# ESP32dj.net
KiCad netlist of a schematic drawn in EasyEDA Pro
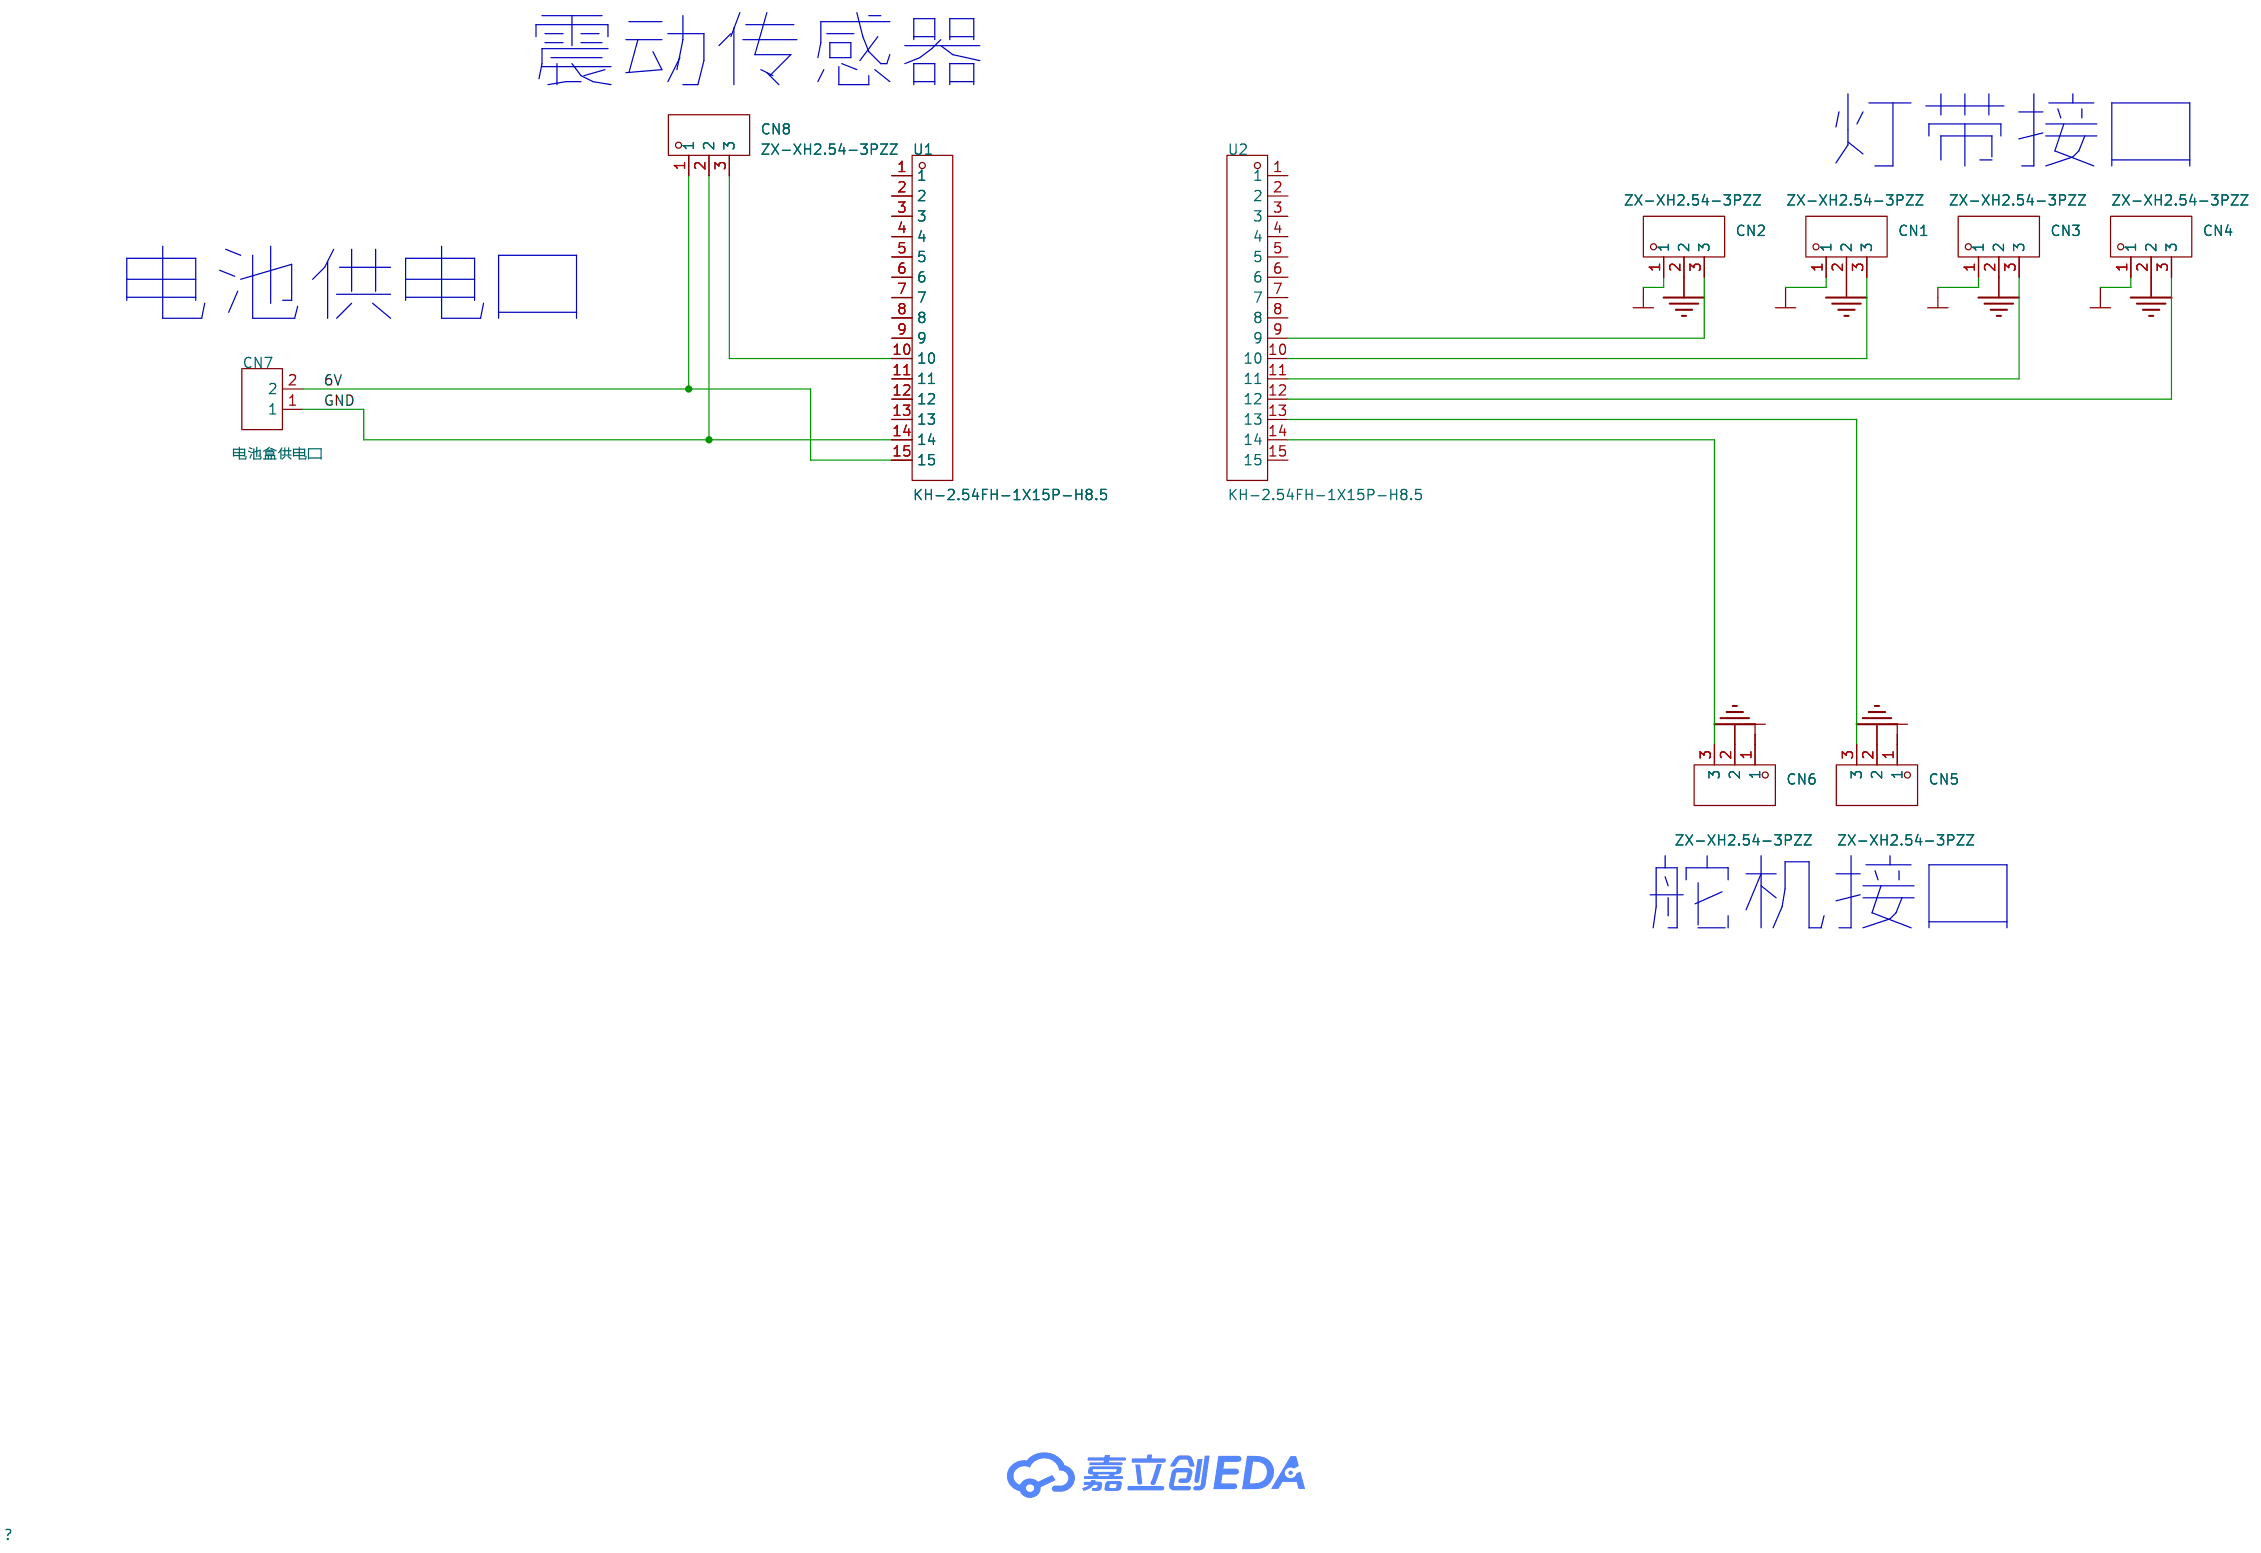
[diagram p0: schematic sheet]

(export (version "E")
  (design (tool "Eeschema 10.0.6"))
  (components
    (comp (ref "CN1")
      (value "ZX-XH2.54-3PZZ")
      (footprint "easyedapro:CONN-TH_3P-P2.54_2501S-3P")
      (fields (field (name "Manufacturer") "Megastar(兆星)"))
      (libsource (lib "easyedapro") (part "ZX-XH2.54-3PZZ"))
    )
    (comp (ref "CN2")
      (value "ZX-XH2.54-3PZZ")
      (footprint "easyedapro:CONN-TH_3P-P2.54_2501S-3P")
      (fields (field (name "Manufacturer") "Megastar(兆星)"))
      (libsource (lib "easyedapro") (part "ZX-XH2.54-3PZZ"))
    )
    (comp (ref "CN3")
      (value "ZX-XH2.54-3PZZ")
      (footprint "easyedapro:CONN-TH_3P-P2.54_2501S-3P")
      (fields (field (name "Manufacturer") "Megastar(兆星)"))
      (libsource (lib "easyedapro") (part "ZX-XH2.54-3PZZ"))
    )
    (comp (ref "CN4")
      (value "ZX-XH2.54-3PZZ")
      (footprint "easyedapro:CONN-TH_3P-P2.54_2501S-3P")
      (fields (field (name "Manufacturer") "Megastar(兆星)"))
      (libsource (lib "easyedapro") (part "ZX-XH2.54-3PZZ"))
    )
    (comp (ref "CN5")
      (value "ZX-XH2.54-3PZZ")
      (footprint "easyedapro:CONN-TH_3P-P2.54_2501S-3P")
      (fields (field (name "Manufacturer") "Megastar(兆星)"))
      (libsource (lib "easyedapro") (part "ZX-XH2.54-3PZZ"))
    )
    (comp (ref "CN6")
      (value "ZX-XH2.54-3PZZ")
      (footprint "easyedapro:CONN-TH_3P-P2.54_2501S-3P")
      (fields (field (name "Manufacturer") "Megastar(兆星)"))
      (libsource (lib "easyedapro") (part "ZX-XH2.54-3PZZ"))
    )
    (comp (ref "CN7")
      (value "电池盒供电口")
      (footprint "easyedapro:CONN-TH_2P-P2.50_BX-XH2.54-2PZZ")
      (fields (field (name "Manufacturer") "Bossie(博锡)"))
      (libsource (lib "easyedapro") (part "BX-XH2.54-2PZZ"))
    )
    (comp (ref "CN8")
      (value "ZX-XH2.54-3PZZ")
      (footprint "easyedapro:CONN-TH_3P-P2.54_2501S-3P")
      (fields (field (name "Manufacturer") "Megastar(兆星)"))
      (libsource (lib "easyedapro") (part "ZX-XH2.54-3PZZ"))
    )
    (comp (ref "U1")
      (value "KH-2.54FH-1X15P-H8.5")
      (footprint "easyedapro:HDR-TH_15P-P2.54-V-F")
      (fields (field (name "Manufacturer") "kinghelm(金航标)"))
      (libsource (lib "easyedapro") (part "KH-2.54FH-1X15P-H8.5"))
    )
    (comp (ref "U2")
      (value "KH-2.54FH-1X15P-H8.5")
      (footprint "easyedapro:HDR-TH_15P-P2.54-V-F")
      (fields (field (name "Manufacturer") "kinghelm(金航标)"))
      (libsource (lib "easyedapro") (part "KH-2.54FH-1X15P-H8.5"))
    )
  )
  (nets
    (net (code "1") (name "6V") (class "Default")
      (node (ref "CN1") (pin "1") (pinfunction "1_1") (pintype "unspecified"))
      (node (ref "CN2") (pin "1") (pinfunction "1_1") (pintype "unspecified"))
      (node (ref "CN3") (pin "1") (pinfunction "1_1") (pintype "unspecified"))
      (node (ref "CN4") (pin "1") (pinfunction "1_1") (pintype "unspecified"))
      (node (ref "CN5") (pin "1") (pinfunction "1_1") (pintype "unspecified"))
      (node (ref "CN6") (pin "1") (pinfunction "1_1") (pintype "unspecified"))
      (node (ref "CN7") (pin "2") (pinfunction "2_2") (pintype "unspecified"))
      (node (ref "CN8") (pin "1") (pinfunction "1_1") (pintype "unspecified"))
      (node (ref "U1") (pin "15") (pinfunction "15_15") (pintype "unspecified"))
    )
    (net (code "2") (name "GND") (class "Default")
      (node (ref "CN1") (pin "2") (pinfunction "2_2") (pintype "unspecified"))
      (node (ref "CN2") (pin "2") (pinfunction "2_2") (pintype "unspecified"))
      (node (ref "CN3") (pin "2") (pinfunction "2_2") (pintype "unspecified"))
      (node (ref "CN4") (pin "2") (pinfunction "2_2") (pintype "unspecified"))
      (node (ref "CN5") (pin "2") (pinfunction "2_2") (pintype "unspecified"))
      (node (ref "CN6") (pin "2") (pinfunction "2_2") (pintype "unspecified"))
      (node (ref "CN7") (pin "1") (pinfunction "1_1") (pintype "unspecified"))
      (node (ref "CN8") (pin "2") (pinfunction "2_2") (pintype "unspecified"))
      (node (ref "U1") (pin "14") (pinfunction "14_14") (pintype "unspecified"))
    )
    (net (code "3") (name "Net-(CN1-Pad3)") (class "Default")
      (node (ref "CN1") (pin "3") (pinfunction "3_3") (pintype "unspecified"))
      (node (ref "U2") (pin "10") (pinfunction "10_10") (pintype "unspecified"))
    )
    (net (code "4") (name "Net-(CN2-Pad3)") (class "Default")
      (node (ref "CN2") (pin "3") (pinfunction "3_3") (pintype "unspecified"))
      (node (ref "U2") (pin "9") (pinfunction "9_9") (pintype "unspecified"))
    )
    (net (code "5") (name "Net-(CN3-Pad3)") (class "Default")
      (node (ref "CN3") (pin "3") (pinfunction "3_3") (pintype "unspecified"))
      (node (ref "U2") (pin "11") (pinfunction "11_11") (pintype "unspecified"))
    )
    (net (code "6") (name "Net-(CN4-Pad3)") (class "Default")
      (node (ref "CN4") (pin "3") (pinfunction "3_3") (pintype "unspecified"))
      (node (ref "U2") (pin "12") (pinfunction "12_12") (pintype "unspecified"))
    )
    (net (code "7") (name "Net-(CN5-Pad3)") (class "Default")
      (node (ref "CN5") (pin "3") (pinfunction "3_3") (pintype "unspecified"))
      (node (ref "U2") (pin "13") (pinfunction "13_13") (pintype "unspecified"))
    )
    (net (code "8") (name "Net-(CN6-Pad3)") (class "Default")
      (node (ref "CN6") (pin "3") (pinfunction "3_3") (pintype "unspecified"))
      (node (ref "U2") (pin "14") (pinfunction "14_14") (pintype "unspecified"))
    )
    (net (code "9") (name "Net-(CN8-Pad3)") (class "Default")
      (node (ref "CN8") (pin "3") (pinfunction "3_3") (pintype "unspecified"))
      (node (ref "U1") (pin "10") (pinfunction "10_10") (pintype "unspecified"))
    )
    (net (code "10") (name "unconnected-(U1-Pad1)") (class "Default")
      (node (ref "U1") (pin "1") (pinfunction "1_1") (pintype "unspecified"))
    )
    (net (code "11") (name "unconnected-(U1-Pad2)") (class "Default")
      (node (ref "U1") (pin "2") (pinfunction "2_2") (pintype "unspecified"))
    )
    (net (code "12") (name "unconnected-(U1-Pad3)") (class "Default")
      (node (ref "U1") (pin "3") (pinfunction "3_3") (pintype "unspecified"))
    )
    (net (code "13") (name "unconnected-(U1-Pad4)") (class "Default")
      (node (ref "U1") (pin "4") (pinfunction "4_4") (pintype "unspecified"))
    )
    (net (code "14") (name "unconnected-(U1-Pad5)") (class "Default")
      (node (ref "U1") (pin "5") (pinfunction "5_5") (pintype "unspecified"))
    )
    (net (code "15") (name "unconnected-(U1-Pad6)") (class "Default")
      (node (ref "U1") (pin "6") (pinfunction "6_6") (pintype "unspecified"))
    )
    (net (code "16") (name "unconnected-(U1-Pad7)") (class "Default")
      (node (ref "U1") (pin "7") (pinfunction "7_7") (pintype "unspecified"))
    )
    (net (code "17") (name "unconnected-(U1-Pad8)") (class "Default")
      (node (ref "U1") (pin "8") (pinfunction "8_8") (pintype "unspecified"))
    )
    (net (code "18") (name "unconnected-(U1-Pad9)") (class "Default")
      (node (ref "U1") (pin "9") (pinfunction "9_9") (pintype "unspecified"))
    )
    (net (code "19") (name "unconnected-(U1-Pad11)") (class "Default")
      (node (ref "U1") (pin "11") (pinfunction "11_11") (pintype "unspecified"))
    )
    (net (code "20") (name "unconnected-(U1-Pad12)") (class "Default")
      (node (ref "U1") (pin "12") (pinfunction "12_12") (pintype "unspecified"))
    )
    (net (code "21") (name "unconnected-(U1-Pad13)") (class "Default")
      (node (ref "U1") (pin "13") (pinfunction "13_13") (pintype "unspecified"))
    )
    (net (code "22") (name "unconnected-(U2-Pad1)") (class "Default")
      (node (ref "U2") (pin "1") (pinfunction "1_1") (pintype "unspecified"))
    )
    (net (code "23") (name "unconnected-(U2-Pad2)") (class "Default")
      (node (ref "U2") (pin "2") (pinfunction "2_2") (pintype "unspecified"))
    )
    (net (code "24") (name "unconnected-(U2-Pad3)") (class "Default")
      (node (ref "U2") (pin "3") (pinfunction "3_3") (pintype "unspecified"))
    )
    (net (code "25") (name "unconnected-(U2-Pad4)") (class "Default")
      (node (ref "U2") (pin "4") (pinfunction "4_4") (pintype "unspecified"))
    )
    (net (code "26") (name "unconnected-(U2-Pad5)") (class "Default")
      (node (ref "U2") (pin "5") (pinfunction "5_5") (pintype "unspecified"))
    )
    (net (code "27") (name "unconnected-(U2-Pad6)") (class "Default")
      (node (ref "U2") (pin "6") (pinfunction "6_6") (pintype "unspecified"))
    )
    (net (code "28") (name "unconnected-(U2-Pad7)") (class "Default")
      (node (ref "U2") (pin "7") (pinfunction "7_7") (pintype "unspecified"))
    )
    (net (code "29") (name "unconnected-(U2-Pad8)") (class "Default")
      (node (ref "U2") (pin "8") (pinfunction "8_8") (pintype "unspecified"))
    )
    (net (code "30") (name "unconnected-(U2-Pad15)") (class "Default")
      (node (ref "U2") (pin "15") (pinfunction "15_15") (pintype "unspecified"))
    )
  )
)
